# Transmitter_PCB.net
KiCad netlist of a schematic drawn in EAGLE
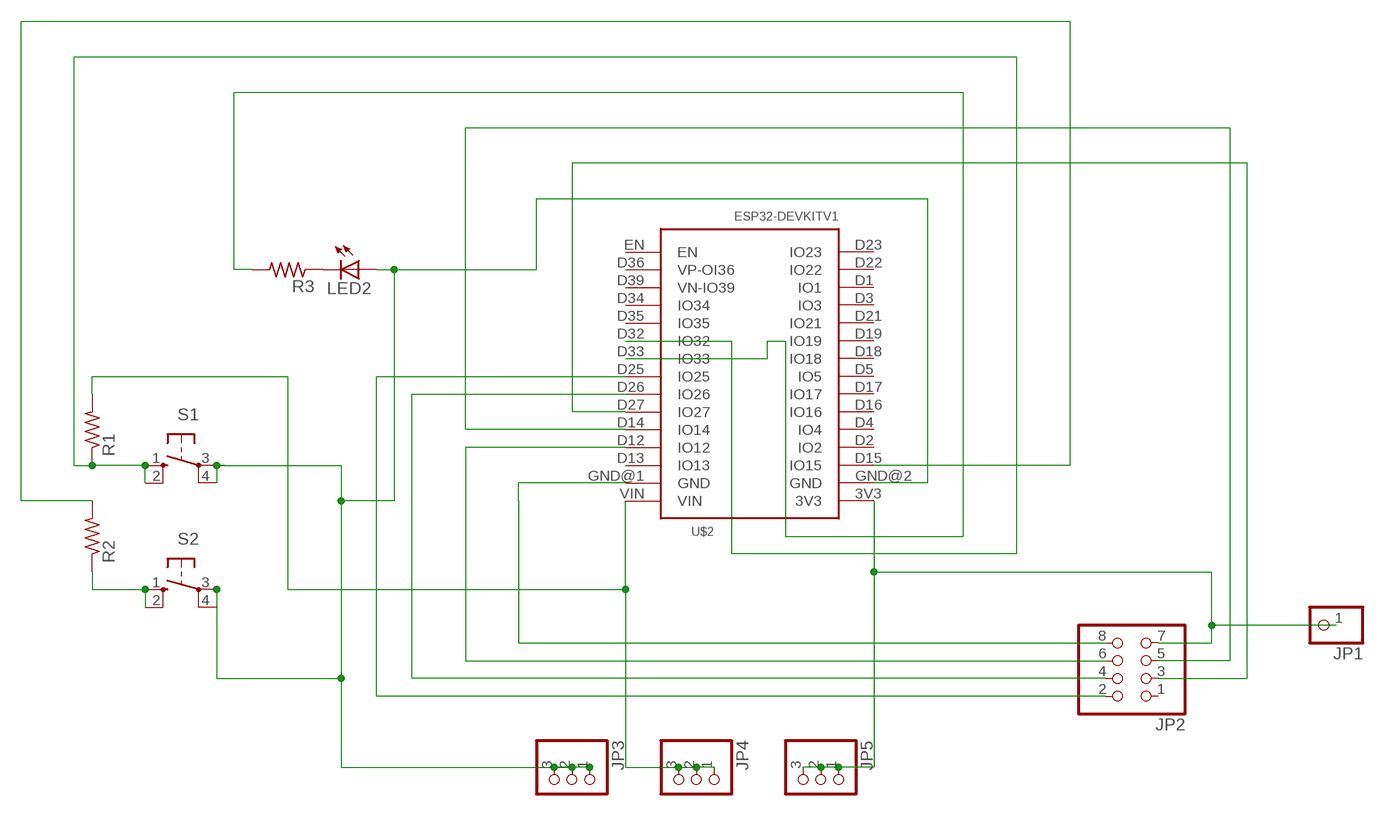
[diagram p0: schematic, sheet 1]

(export (version "E")
  (design (tool "Eeschema 10.0.6"))
  (components
    (comp (ref "JP1")
      (value "PINHD-1X1")
      (footprint "eagle-import:1X01")
      (libsource (lib "eagle-import") (part "PINHD-1X1"))
    )
    (comp (ref "JP2")
      (value "PINHD-2X4")
      (footprint "eagle-import:2X04")
      (libsource (lib "eagle-import") (part "PINHD-2X4"))
    )
    (comp (ref "JP3")
      (value "PINHD-1X3")
      (footprint "eagle-import:1X03")
      (libsource (lib "eagle-import") (part "PINHD-1X3"))
    )
    (comp (ref "JP4")
      (value "PINHD-1X3")
      (footprint "eagle-import:1X03")
      (libsource (lib "eagle-import") (part "PINHD-1X3"))
    )
    (comp (ref "JP5")
      (value "PINHD-1X3")
      (footprint "eagle-import:1X03")
      (libsource (lib "eagle-import") (part "PINHD-1X3"))
    )
    (comp (ref "LED2")
      (value "LED5MM")
      (footprint "eagle-import:LED5MM")
      (libsource (lib "eagle-import") (part "LED5MM"))
    )
    (comp (ref "R1")
      (value "R-US_0207/7")
      (footprint "eagle-import:0207_7")
      (libsource (lib "eagle-import") (part "R-US_0207/7"))
    )
    (comp (ref "R2")
      (value "R-US_0207/7")
      (footprint "eagle-import:0207_7")
      (libsource (lib "eagle-import") (part "R-US_0207/7"))
    )
    (comp (ref "R3")
      (value "R-US_0207/7")
      (footprint "eagle-import:0207_7")
      (libsource (lib "eagle-import") (part "R-US_0207/7"))
    )
    (comp (ref "S1")
      (value "10-XX")
      (footprint "eagle-import:B3F-10XX")
      (fields (field (name "MPN") "B3F-1000"))
      (libsource (lib "eagle-import") (part "10-XX"))
    )
    (comp (ref "S2")
      (value "10-XX")
      (footprint "eagle-import:B3F-10XX")
      (fields (field (name "MPN") "B3F-1000"))
      (libsource (lib "eagle-import") (part "10-XX"))
    )
    (comp (ref "U$2")
      (value "ESP32DEVKITV1")
      (footprint "eagle-import:ESP32-DEVKITV1")
      (libsource (lib "eagle-import") (part "ESP32DEVKITV1"))
    )
  )
  (nets
    (net (code "1") (name "Net-(JP1-Pad1)") (class "Default")
      (node (ref "JP1") (pin "1") (pinfunction "1_1") (pintype "passive"))
      (node (ref "JP2") (pin "7") (pinfunction "7_7") (pintype "passive"))
      (node (ref "JP5") (pin "1") (pinfunction "1_1") (pintype "passive"))
      (node (ref "JP5") (pin "2") (pinfunction "2_2") (pintype "passive"))
      (node (ref "JP5") (pin "3") (pinfunction "3_3") (pintype "passive"))
      (node (ref "U$2") (pin "3V3") (pinfunction "3V3_3V3") (pintype "bidirectional"))
    )
    (net (code "2") (name "Net-(JP2-Pad8)") (class "Default")
      (node (ref "JP2") (pin "8") (pinfunction "8_8") (pintype "passive"))
      (node (ref "U$2") (pin "GND@1") (pinfunction "GND_GND@1") (pintype "bidirectional"))
    )
    (net (code "3") (name "Net-(JP4-Pad1)") (class "Default")
      (node (ref "JP4") (pin "1") (pinfunction "1_1") (pintype "passive"))
      (node (ref "JP4") (pin "2") (pinfunction "2_2") (pintype "passive"))
      (node (ref "JP4") (pin "3") (pinfunction "3_3") (pintype "passive"))
      (node (ref "R1") (pin "2") (pinfunction "2_2") (pintype "passive"))
      (node (ref "U$2") (pin "VIN") (pinfunction "VIN_VIN") (pintype "bidirectional"))
    )
    (net (code "4") (name "Net-(LED2-C)") (class "Default")
      (node (ref "LED2") (pin "K") (pinfunction "C_K") (pintype "passive"))
      (node (ref "R3") (pin "1") (pinfunction "1_1") (pintype "passive"))
    )
    (net (code "5") (name "Net-(S1-P)") (class "Default")
      (node (ref "JP3") (pin "1") (pinfunction "1_1") (pintype "passive"))
      (node (ref "JP3") (pin "2") (pinfunction "2_2") (pintype "passive"))
      (node (ref "JP3") (pin "3") (pinfunction "3_3") (pintype "passive"))
      (node (ref "LED2") (pin "A") (pinfunction "A_A") (pintype "passive"))
      (node (ref "S1") (pin "3") (pinfunction "P_3") (pintype "passive"))
      (node (ref "S1") (pin "4") (pinfunction "P1_4") (pintype "passive"))
      (node (ref "S2") (pin "3") (pinfunction "P_3") (pintype "passive"))
      (node (ref "S2") (pin "4") (pinfunction "P1_4") (pintype "passive"))
      (node (ref "U$2") (pin "GND@2") (pinfunction "GND_GND@2") (pintype "bidirectional"))
    )
    (net (code "6") (name "Net-(S1-S)") (class "Default")
      (node (ref "R1") (pin "1") (pinfunction "1_1") (pintype "passive"))
      (node (ref "S1") (pin "1") (pinfunction "S_1") (pintype "passive"))
      (node (ref "S1") (pin "2") (pinfunction "S1_2") (pintype "passive"))
      (node (ref "U$2") (pin "D32") (pinfunction "IO32_D32") (pintype "bidirectional"))
    )
    (net (code "7") (name "Net-(S2-S)") (class "Default")
      (node (ref "R2") (pin "1") (pinfunction "1_1") (pintype "passive"))
      (node (ref "S2") (pin "1") (pinfunction "S_1") (pintype "passive"))
      (node (ref "S2") (pin "2") (pinfunction "S1_2") (pintype "passive"))
    )
    (net (code "8") (name "Net-(U$2-IO12)") (class "Default")
      (node (ref "JP2") (pin "6") (pinfunction "6_6") (pintype "passive"))
      (node (ref "U$2") (pin "D12") (pinfunction "IO12_D12") (pintype "bidirectional"))
    )
    (net (code "9") (name "Net-(U$2-IO14)") (class "Default")
      (node (ref "JP2") (pin "5") (pinfunction "5_5") (pintype "passive"))
      (node (ref "U$2") (pin "D14") (pinfunction "IO14_D14") (pintype "bidirectional"))
    )
    (net (code "10") (name "Net-(U$2-IO15)") (class "Default")
      (node (ref "R2") (pin "2") (pinfunction "2_2") (pintype "passive"))
      (node (ref "U$2") (pin "D15") (pinfunction "IO15_D15") (pintype "bidirectional"))
    )
    (net (code "11") (name "Net-(U$2-IO25)") (class "Default")
      (node (ref "JP2") (pin "2") (pinfunction "2_2") (pintype "passive"))
      (node (ref "U$2") (pin "D25") (pinfunction "IO25_D25") (pintype "bidirectional"))
    )
    (net (code "12") (name "Net-(U$2-IO26)") (class "Default")
      (node (ref "JP2") (pin "4") (pinfunction "4_4") (pintype "passive"))
      (node (ref "U$2") (pin "D26") (pinfunction "IO26_D26") (pintype "bidirectional"))
    )
    (net (code "13") (name "Net-(U$2-IO27)") (class "Default")
      (node (ref "JP2") (pin "3") (pinfunction "3_3") (pintype "passive"))
      (node (ref "U$2") (pin "D27") (pinfunction "IO27_D27") (pintype "bidirectional"))
    )
    (net (code "14") (name "Net-(U$2-IO33)") (class "Default")
      (node (ref "R3") (pin "2") (pinfunction "2_2") (pintype "passive"))
      (node (ref "U$2") (pin "D33") (pinfunction "IO33_D33") (pintype "bidirectional"))
    )
    (net (code "15") (name "unconnected-(JP2-Pad1)") (class "Default")
      (node (ref "JP2") (pin "1") (pinfunction "1_1") (pintype "passive"))
    )
    (net (code "16") (name "unconnected-(U$2-IO1-PadD1)") (class "Default")
      (node (ref "U$2") (pin "D1") (pinfunction "IO1_D1") (pintype "bidirectional"))
    )
    (net (code "17") (name "unconnected-(U$2-IO2-PadD2)") (class "Default")
      (node (ref "U$2") (pin "D2") (pinfunction "IO2_D2") (pintype "bidirectional"))
    )
    (net (code "18") (name "unconnected-(U$2-IO3-PadD3)") (class "Default")
      (node (ref "U$2") (pin "D3") (pinfunction "IO3_D3") (pintype "bidirectional"))
    )
    (net (code "19") (name "unconnected-(U$2-IO4-PadD4)") (class "Default")
      (node (ref "U$2") (pin "D4") (pinfunction "IO4_D4") (pintype "bidirectional"))
    )
    (net (code "20") (name "unconnected-(U$2-IO5-PadD5)") (class "Default")
      (node (ref "U$2") (pin "D5") (pinfunction "IO5_D5") (pintype "bidirectional"))
    )
    (net (code "21") (name "unconnected-(U$2-IO13-PadD13)") (class "Default")
      (node (ref "U$2") (pin "D13") (pinfunction "IO13_D13") (pintype "bidirectional"))
    )
    (net (code "22") (name "unconnected-(U$2-IO16-PadD16)") (class "Default")
      (node (ref "U$2") (pin "D16") (pinfunction "IO16_D16") (pintype "bidirectional"))
    )
    (net (code "23") (name "unconnected-(U$2-IO17-PadD17)") (class "Default")
      (node (ref "U$2") (pin "D17") (pinfunction "IO17_D17") (pintype "bidirectional"))
    )
    (net (code "24") (name "unconnected-(U$2-IO18-PadD18)") (class "Default")
      (node (ref "U$2") (pin "D18") (pinfunction "IO18_D18") (pintype "bidirectional"))
    )
    (net (code "25") (name "unconnected-(U$2-IO19-PadD19)") (class "Default")
      (node (ref "U$2") (pin "D19") (pinfunction "IO19_D19") (pintype "bidirectional"))
    )
    (net (code "26") (name "unconnected-(U$2-IO21-PadD21)") (class "Default")
      (node (ref "U$2") (pin "D21") (pinfunction "IO21_D21") (pintype "bidirectional"))
    )
    (net (code "27") (name "unconnected-(U$2-IO22-PadD22)") (class "Default")
      (node (ref "U$2") (pin "D22") (pinfunction "IO22_D22") (pintype "bidirectional"))
    )
    (net (code "28") (name "unconnected-(U$2-IO23-PadD23)") (class "Default")
      (node (ref "U$2") (pin "D23") (pinfunction "IO23_D23") (pintype "bidirectional"))
    )
    (net (code "29") (name "unconnected-(U$2-IO34-PadD34)") (class "Default")
      (node (ref "U$2") (pin "D34") (pinfunction "IO34_D34") (pintype "bidirectional"))
    )
    (net (code "30") (name "unconnected-(U$2-IO35-PadD35)") (class "Default")
      (node (ref "U$2") (pin "D35") (pinfunction "IO35_D35") (pintype "bidirectional"))
    )
    (net (code "31") (name "unconnected-(U$2-PadEN)") (class "Default")
      (node (ref "U$2") (pin "EN") (pinfunction "EN_EN") (pintype "bidirectional"))
    )
    (net (code "32") (name "unconnected-(U$2-VN-IO39-PadD39)") (class "Default")
      (node (ref "U$2") (pin "D39") (pinfunction "VN-IO39_D39") (pintype "bidirectional"))
    )
    (net (code "33") (name "unconnected-(U$2-VP-OI36-PadD36)") (class "Default")
      (node (ref "U$2") (pin "D36") (pinfunction "VP-OI36_D36") (pintype "bidirectional"))
    )
  )
)
